# REV2.net
KiCad netlist of a schematic drawn in EAGLE
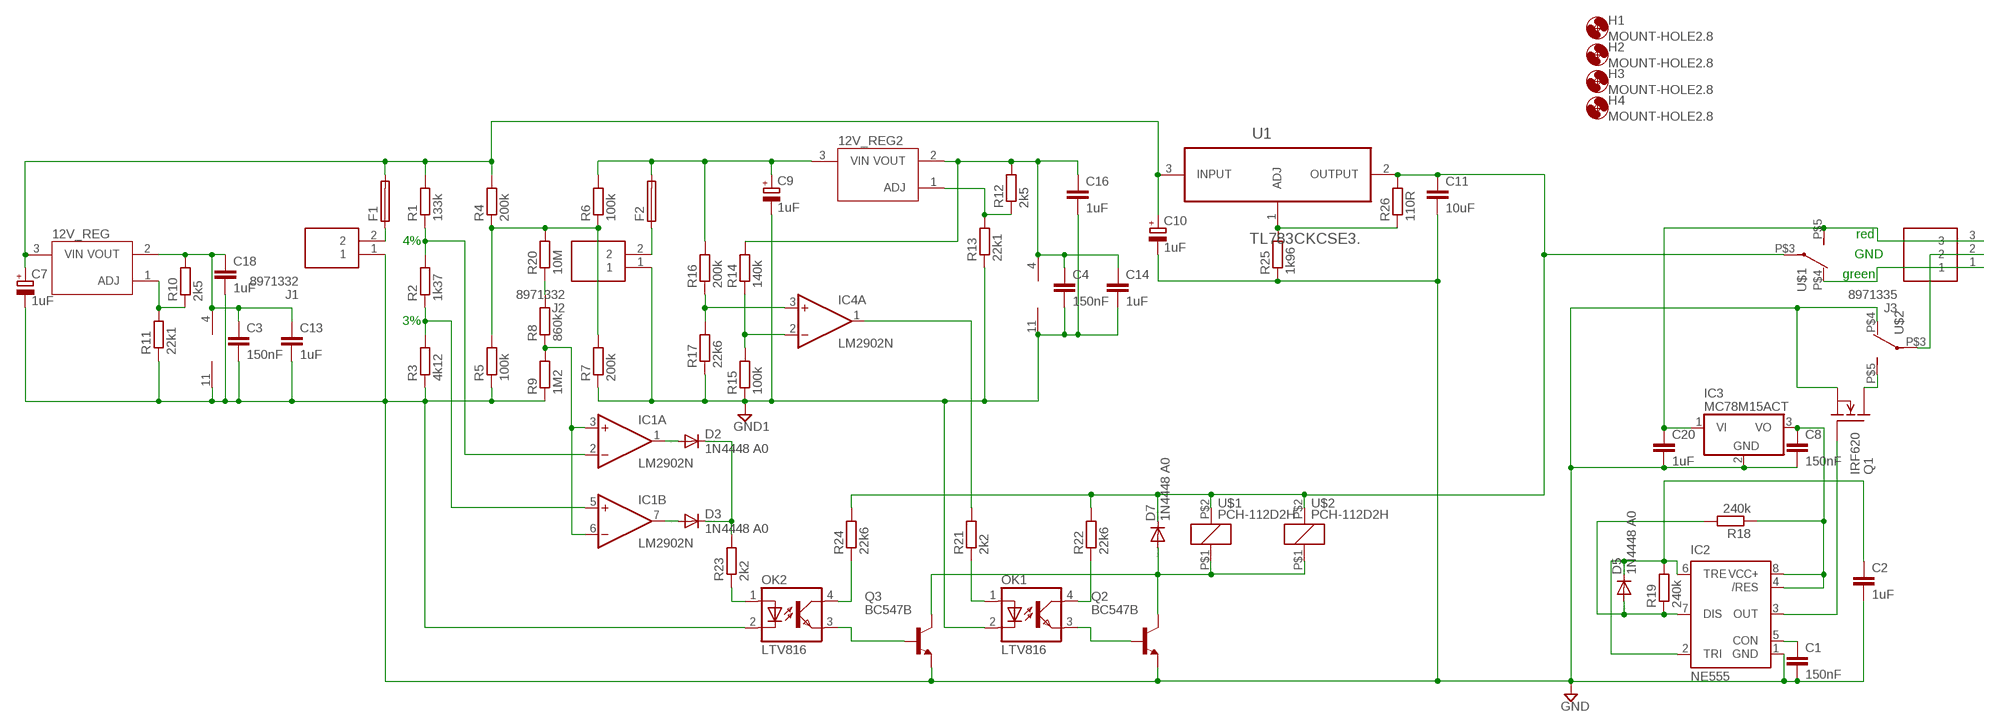
[diagram p0: schematic, sheet 1]

(export (version "E")
  (design (tool "Eeschema 10.0.6"))
  (components
    (comp (ref "12V_REG")
      (value "LR8LR8")
      (footprint "eagle-import:TO92-LINE")
      (libsource (lib "eagle-import") (part "LR8LR8"))
    )
    (comp (ref "12V_REG2")
      (value "LR8LR8")
      (footprint "eagle-import:TO92-LINE")
      (libsource (lib "eagle-import") (part "LR8LR8"))
    )
    (comp (ref "C1")
      (value "150nF")
      (footprint "eagle-import:C050-024X044")
      (libsource (lib "eagle-import") (part "C-EU050-024X044"))
    )
    (comp (ref "C2")
      (value "1uF")
      (footprint "eagle-import:C025-030X050")
      (libsource (lib "eagle-import") (part "C-EU025-030X050"))
    )
    (comp (ref "C3")
      (value "150nF")
      (footprint "eagle-import:C050-024X044")
      (libsource (lib "eagle-import") (part "C-EU050-024X044"))
    )
    (comp (ref "C4")
      (value "150nF")
      (footprint "eagle-import:C050-024X044")
      (libsource (lib "eagle-import") (part "C-EU050-024X044"))
    )
    (comp (ref "C7")
      (value "1uF")
      (footprint "eagle-import:E3,5-8")
      (libsource (lib "eagle-import") (part "CPOL-EUE3.5-8"))
    )
    (comp (ref "C8")
      (value "150nF")
      (footprint "eagle-import:C050-024X044")
      (libsource (lib "eagle-import") (part "C-EU050-024X044"))
    )
    (comp (ref "C9")
      (value "1uF")
      (footprint "eagle-import:E3,5-8")
      (libsource (lib "eagle-import") (part "CPOL-EUE3.5-8"))
    )
    (comp (ref "C10")
      (value "1uF")
      (footprint "eagle-import:E3,5-8")
      (libsource (lib "eagle-import") (part "CPOL-EUE3.5-8"))
    )
    (comp (ref "C11")
      (value "10uF")
      (footprint "eagle-import:C050-075X075")
      (libsource (lib "eagle-import") (part "C-EU050-075X075"))
    )
    (comp (ref "C13")
      (value "1uF")
      (footprint "eagle-import:C025-030X050")
      (libsource (lib "eagle-import") (part "C-EU025-030X050"))
    )
    (comp (ref "C14")
      (value "1uF")
      (footprint "eagle-import:C025-030X050")
      (libsource (lib "eagle-import") (part "C-EU025-030X050"))
    )
    (comp (ref "C16")
      (value "1uF")
      (footprint "eagle-import:C025-030X050")
      (libsource (lib "eagle-import") (part "C-EU025-030X050"))
    )
    (comp (ref "C18")
      (value "1uF")
      (footprint "eagle-import:C025-030X050")
      (libsource (lib "eagle-import") (part "C-EU025-030X050"))
    )
    (comp (ref "C20")
      (value "1uF")
      (footprint "eagle-import:C025-030X050")
      (libsource (lib "eagle-import") (part "C-EU025-030X050"))
    )
    (comp (ref "D2")
      (value "1N4448 A0")
      (footprint "eagle-import:DO35-10")
      (libsource (lib "eagle-import") (part "1N4446"))
    )
    (comp (ref "D3")
      (value "1N4448 A0")
      (footprint "eagle-import:DO35-10")
      (libsource (lib "eagle-import") (part "1N4446"))
    )
    (comp (ref "D5")
      (value "1N4448 A0")
      (footprint "eagle-import:DO35-10")
      (libsource (lib "eagle-import") (part "1N4446"))
    )
    (comp (ref "D7")
      (value "1N4448 A0")
      (footprint "eagle-import:DO35-10")
      (libsource (lib "eagle-import") (part "1N4446"))
    )
    (comp (ref "F1")
      (value "GSH15")
      (footprint "eagle-import:GSH15")
      (fields (field (name "MPN") "64900001039"))
      (libsource (lib "eagle-import") (part "GSH15"))
    )
    (comp (ref "F2")
      (value "GSH15")
      (footprint "eagle-import:GSH15")
      (fields (field (name "MPN") "64900001039"))
      (libsource (lib "eagle-import") (part "GSH15"))
    )
    (comp (ref "H1")
      (value "MOUNT-HOLE2.8")
      (footprint "eagle-import:2,8")
      (libsource (lib "eagle-import") (part "MOUNT-HOLE2.8"))
    )
    (comp (ref "H2")
      (value "MOUNT-HOLE2.8")
      (footprint "eagle-import:2,8")
      (libsource (lib "eagle-import") (part "MOUNT-HOLE2.8"))
    )
    (comp (ref "H3")
      (value "MOUNT-HOLE2.8")
      (footprint "eagle-import:2,8")
      (libsource (lib "eagle-import") (part "MOUNT-HOLE2.8"))
    )
    (comp (ref "H4")
      (value "MOUNT-HOLE2.8")
      (footprint "eagle-import:2,8")
      (libsource (lib "eagle-import") (part "MOUNT-HOLE2.8"))
    )
    (comp (ref "IC1")
      (value "LM2902N")
      (footprint "eagle-import:DIL14")
      (libsource (lib "eagle-import") (part "LM2902N"))
    )
    (comp (ref "IC2")
      (value "NE555")
      (footprint "eagle-import:DIL-08")
      (fields (field (name "MF") "Arrow Electronics") (field (name "MPN") "NE555N"))
      (libsource (lib "eagle-import") (part "NE555"))
    )
    (comp (ref "IC3")
      (value "MC78M15ACT")
      (footprint "eagle-import:TO220V")
      (libsource (lib "eagle-import") (part "MC78MT15AC"))
    )
    (comp (ref "IC4")
      (value "LM2902N")
      (footprint "eagle-import:DIL14")
      (libsource (lib "eagle-import") (part "LM2902N"))
    )
    (comp (ref "J1")
      (value "8971332")
      (footprint "eagle-import:SHDR2W90P0X350_1X2_700X700X850")
      (libsource (lib "eagle-import") (part "8971332"))
    )
    (comp (ref "J2")
      (value "8971332")
      (footprint "eagle-import:SHDR2W90P0X350_1X2_700X700X850")
      (libsource (lib "eagle-import") (part "8971332"))
    )
    (comp (ref "J3")
      (value "8971335")
      (footprint "eagle-import:SHDR3W90P0X350_1X3_1050X700X85")
      (libsource (lib "eagle-import") (part "8971335"))
    )
    (comp (ref "OK1")
      (value "LTV816")
      (footprint "eagle-import:DIL04")
      (libsource (lib "eagle-import") (part "LTV816"))
    )
    (comp (ref "OK2")
      (value "LTV816")
      (footprint "eagle-import:DIL04")
      (libsource (lib "eagle-import") (part "LTV816"))
    )
    (comp (ref "Q1")
      (value "IRF620")
      (footprint "eagle-import:TO220")
      (libsource (lib "eagle-import") (part "IRF620"))
    )
    (comp (ref "Q2")
      (value "BC547B")
      (footprint "eagle-import:TO92")
      (libsource (lib "eagle-import") (part "BC547B"))
    )
    (comp (ref "Q3")
      (value "BC547B")
      (footprint "eagle-import:TO92")
      (libsource (lib "eagle-import") (part "BC547B"))
    )
    (comp (ref "R1")
      (value "133k")
      (footprint "eagle-import:0207_10")
      (libsource (lib "eagle-import") (part "R-EU_0207/10"))
    )
    (comp (ref "R2")
      (value "1k37")
      (footprint "eagle-import:0207_10")
      (libsource (lib "eagle-import") (part "R-EU_0207/10"))
    )
    (comp (ref "R3")
      (value "4k12")
      (footprint "eagle-import:0207_10")
      (libsource (lib "eagle-import") (part "R-EU_0207/10"))
    )
    (comp (ref "R4")
      (value "200k")
      (footprint "eagle-import:0207_10")
      (libsource (lib "eagle-import") (part "R-EU_0207/10"))
    )
    (comp (ref "R5")
      (value "100k")
      (footprint "eagle-import:0207_10")
      (libsource (lib "eagle-import") (part "R-EU_0207/10"))
    )
    (comp (ref "R6")
      (value "100k")
      (footprint "eagle-import:0207_10")
      (libsource (lib "eagle-import") (part "R-EU_0207/10"))
    )
    (comp (ref "R7")
      (value "200k")
      (footprint "eagle-import:0207_10")
      (libsource (lib "eagle-import") (part "R-EU_0207/10"))
    )
    (comp (ref "R8")
      (value "860k")
      (footprint "eagle-import:0207_10")
      (libsource (lib "eagle-import") (part "R-EU_0207/10"))
    )
    (comp (ref "R9")
      (value "1M2")
      (footprint "eagle-import:0207_10")
      (libsource (lib "eagle-import") (part "R-EU_0207/10"))
    )
    (comp (ref "R10")
      (value "2k5")
      (footprint "eagle-import:0207_10")
      (libsource (lib "eagle-import") (part "R-EU_0207/10"))
    )
    (comp (ref "R11")
      (value "22k1")
      (footprint "eagle-import:0207_10")
      (libsource (lib "eagle-import") (part "R-EU_0207/10"))
    )
    (comp (ref "R12")
      (value "2k5")
      (footprint "eagle-import:0207_10")
      (libsource (lib "eagle-import") (part "R-EU_0207/10"))
    )
    (comp (ref "R13")
      (value "22k1")
      (footprint "eagle-import:0207_10")
      (libsource (lib "eagle-import") (part "R-EU_0207/10"))
    )
    (comp (ref "R14")
      (value "140k")
      (footprint "eagle-import:0207_10")
      (libsource (lib "eagle-import") (part "R-EU_0207/10"))
    )
    (comp (ref "R15")
      (value "100k")
      (footprint "eagle-import:0207_10")
      (libsource (lib "eagle-import") (part "R-EU_0207/10"))
    )
    (comp (ref "R16")
      (value "200k")
      (footprint "eagle-import:0207_10")
      (libsource (lib "eagle-import") (part "R-EU_0207/10"))
    )
    (comp (ref "R17")
      (value "22k6")
      (footprint "eagle-import:0207_10")
      (libsource (lib "eagle-import") (part "R-EU_0207/10"))
    )
    (comp (ref "R18")
      (value "240k")
      (footprint "eagle-import:0207_10")
      (libsource (lib "eagle-import") (part "R-EU_0207/10"))
    )
    (comp (ref "R19")
      (value "240k")
      (footprint "eagle-import:0207_10")
      (libsource (lib "eagle-import") (part "R-EU_0207/10"))
    )
    (comp (ref "R20")
      (value "10M")
      (footprint "eagle-import:0207_10")
      (libsource (lib "eagle-import") (part "R-EU_0207/10"))
    )
    (comp (ref "R21")
      (value "2k2")
      (footprint "eagle-import:0207_10")
      (libsource (lib "eagle-import") (part "R-EU_0207/10"))
    )
    (comp (ref "R22")
      (value "22k6")
      (footprint "eagle-import:0207_10")
      (libsource (lib "eagle-import") (part "R-EU_0207/10"))
    )
    (comp (ref "R23")
      (value "2k2")
      (footprint "eagle-import:0207_10")
      (libsource (lib "eagle-import") (part "R-EU_0207/10"))
    )
    (comp (ref "R24")
      (value "22k6")
      (footprint "eagle-import:0207_10")
      (libsource (lib "eagle-import") (part "R-EU_0207/10"))
    )
    (comp (ref "R25")
      (value "1k96")
      (footprint "eagle-import:0309_10")
      (libsource (lib "eagle-import") (part "R-EU_0309/10"))
    )
    (comp (ref "R26")
      (value "110R")
      (footprint "eagle-import:0309_10")
      (libsource (lib "eagle-import") (part "R-EU_0309/10"))
    )
    (comp (ref "U$1")
      (value "PCH-112D2H")
      (footprint "eagle-import:PCH-112D2H")
      (libsource (lib "eagle-import") (part "PCH-112D2H"))
    )
    (comp (ref "U$2")
      (value "PCH-112D2H")
      (footprint "eagle-import:PCH-112D2H")
      (libsource (lib "eagle-import") (part "PCH-112D2H"))
    )
    (comp (ref "U1")
      (value "TL783CKCSE3.")
      (footprint "eagle-import:TO254P457X1016X2222-3P")
      (libsource (lib "eagle-import") (part "TL783CKCSE3."))
    )
  )
  (nets
    (net (code "1") (name "GND") (class "Default")
      (node (ref "C1") (pin "2") (pinfunction "2_2") (pintype "passive"))
      (node (ref "C10") (pin "-") (pinfunction "-_-") (pintype "passive"))
      (node (ref "C11") (pin "2") (pinfunction "2_2") (pintype "passive"))
      (node (ref "C13") (pin "2") (pinfunction "2_2") (pintype "passive"))
      (node (ref "C18") (pin "2") (pinfunction "2_2") (pintype "passive"))
      (node (ref "C2") (pin "2") (pinfunction "2_2") (pintype "passive"))
      (node (ref "C20") (pin "2") (pinfunction "2_2") (pintype "passive"))
      (node (ref "C3") (pin "2") (pinfunction "2_2") (pintype "passive"))
      (node (ref "C7") (pin "-") (pinfunction "-_-") (pintype "passive"))
      (node (ref "C8") (pin "2") (pinfunction "2_2") (pintype "passive"))
      (node (ref "IC1") (pin "11") (pinfunction "V-_11") (pintype "power_in"))
      (node (ref "IC2") (pin "1") (pinfunction "GND_1") (pintype "power_in"))
      (node (ref "IC3") (pin "2") (pinfunction "GND_2") (pintype "passive"))
      (node (ref "J1") (pin "1") (pinfunction "1_1") (pintype "bidirectional"))
      (node (ref "OK2") (pin "2") (pinfunction "C_2") (pintype "passive"))
      (node (ref "Q1") (pin "3") (pinfunction "S_3") (pintype "passive"))
      (node (ref "Q2") (pin "1") (pinfunction "E_1") (pintype "passive"))
      (node (ref "Q3") (pin "1") (pinfunction "E_1") (pintype "passive"))
      (node (ref "R11") (pin "1") (pinfunction "1_1") (pintype "passive"))
      (node (ref "R25") (pin "1") (pinfunction "1_1") (pintype "passive"))
      (node (ref "R3") (pin "1") (pinfunction "1_1") (pintype "passive"))
      (node (ref "R5") (pin "1") (pinfunction "1_1") (pintype "passive"))
      (node (ref "R9") (pin "1") (pinfunction "1_1") (pintype "passive"))
      (node (ref "U$2") (pin "P$4") (pinfunction "O_P$4") (pintype "passive"))
    )
    (net (code "2") (name "GND1") (class "Default")
      (node (ref "C14") (pin "2") (pinfunction "2_2") (pintype "passive"))
      (node (ref "C16") (pin "2") (pinfunction "2_2") (pintype "passive"))
      (node (ref "C4") (pin "2") (pinfunction "2_2") (pintype "passive"))
      (node (ref "C9") (pin "-") (pinfunction "-_-") (pintype "passive"))
      (node (ref "IC4") (pin "11") (pinfunction "V-_11") (pintype "power_in"))
      (node (ref "J2") (pin "1") (pinfunction "1_1") (pintype "bidirectional"))
      (node (ref "OK1") (pin "2") (pinfunction "C_2") (pintype "passive"))
      (node (ref "R13") (pin "1") (pinfunction "1_1") (pintype "passive"))
      (node (ref "R15") (pin "1") (pinfunction "1_1") (pintype "passive"))
      (node (ref "R17") (pin "1") (pinfunction "1_1") (pintype "passive"))
      (node (ref "R7") (pin "1") (pinfunction "1_1") (pintype "passive"))
    )
    (net (code "3") (name "Net-(12V_REG-ADJ)") (class "Default")
      (node (ref "12V_REG") (pin "1") (pinfunction "ADJ_1") (pintype "bidirectional"))
      (node (ref "R10") (pin "1") (pinfunction "1_1") (pintype "passive"))
      (node (ref "R11") (pin "2") (pinfunction "2_2") (pintype "passive"))
    )
    (net (code "4") (name "Net-(12V_REG-VIN)") (class "Default")
      (node (ref "12V_REG") (pin "3") (pinfunction "VIN_3") (pintype "bidirectional"))
      (node (ref "C10") (pin "+") (pinfunction "+_+") (pintype "passive"))
      (node (ref "C7") (pin "+") (pinfunction "+_+") (pintype "passive"))
      (node (ref "F1") (pin "2") (pinfunction "2_2") (pintype "passive"))
      (node (ref "R1") (pin "2") (pinfunction "2_2") (pintype "passive"))
      (node (ref "R4") (pin "2") (pinfunction "2_2") (pintype "passive"))
      (node (ref "U1") (pin "3") (pinfunction "INPUT_3") (pintype "input"))
    )
    (net (code "5") (name "Net-(12V_REG-VOUT)") (class "Default")
      (node (ref "12V_REG") (pin "2") (pinfunction "VOUT_2") (pintype "bidirectional"))
      (node (ref "C13") (pin "1") (pinfunction "1_1") (pintype "passive"))
      (node (ref "C18") (pin "1") (pinfunction "1_1") (pintype "passive"))
      (node (ref "C3") (pin "1") (pinfunction "1_1") (pintype "passive"))
      (node (ref "IC1") (pin "4") (pinfunction "V+_4") (pintype "power_in"))
      (node (ref "R10") (pin "2") (pinfunction "2_2") (pintype "passive"))
    )
    (net (code "6") (name "Net-(12V_REG2-ADJ)") (class "Default")
      (node (ref "12V_REG2") (pin "1") (pinfunction "ADJ_1") (pintype "bidirectional"))
      (node (ref "R12") (pin "1") (pinfunction "1_1") (pintype "passive"))
      (node (ref "R13") (pin "2") (pinfunction "2_2") (pintype "passive"))
    )
    (net (code "7") (name "Net-(12V_REG2-VIN)") (class "Default")
      (node (ref "12V_REG2") (pin "3") (pinfunction "VIN_3") (pintype "bidirectional"))
      (node (ref "C9") (pin "+") (pinfunction "+_+") (pintype "passive"))
      (node (ref "F2") (pin "2") (pinfunction "2_2") (pintype "passive"))
      (node (ref "R16") (pin "2") (pinfunction "2_2") (pintype "passive"))
      (node (ref "R6") (pin "2") (pinfunction "2_2") (pintype "passive"))
    )
    (net (code "8") (name "Net-(12V_REG2-VOUT)") (class "Default")
      (node (ref "12V_REG2") (pin "2") (pinfunction "VOUT_2") (pintype "bidirectional"))
      (node (ref "C14") (pin "1") (pinfunction "1_1") (pintype "passive"))
      (node (ref "C16") (pin "1") (pinfunction "1_1") (pintype "passive"))
      (node (ref "C4") (pin "1") (pinfunction "1_1") (pintype "passive"))
      (node (ref "IC4") (pin "4") (pinfunction "V+_4") (pintype "power_in"))
      (node (ref "R12") (pin "2") (pinfunction "2_2") (pintype "passive"))
      (node (ref "R14") (pin "2") (pinfunction "2_2") (pintype "passive"))
    )
    (net (code "9") (name "Net-(D2-PadC)") (class "Default")
      (node (ref "D2") (pin "C") (pinfunction "C_C") (pintype "passive"))
      (node (ref "D3") (pin "C") (pinfunction "C_C") (pintype "passive"))
      (node (ref "R23") (pin "2") (pinfunction "2_2") (pintype "passive"))
    )
    (net (code "10") (name "Net-(F1-Pad1)") (class "Default")
      (node (ref "F1") (pin "1") (pinfunction "1_1") (pintype "passive"))
      (node (ref "J1") (pin "2") (pinfunction "2_2") (pintype "bidirectional"))
    )
    (net (code "11") (name "Net-(F2-Pad1)") (class "Default")
      (node (ref "F2") (pin "1") (pinfunction "1_1") (pintype "passive"))
      (node (ref "J2") (pin "2") (pinfunction "2_2") (pintype "bidirectional"))
    )
    (net (code "12") (name "Net-(IC1A-+IN)") (class "Default")
      (node (ref "IC1") (pin "3") (pinfunction "+IN_3") (pintype "input"))
      (node (ref "IC1") (pin "6") (pinfunction "-IN_6") (pintype "input"))
      (node (ref "R8") (pin "1") (pinfunction "1_1") (pintype "passive"))
      (node (ref "R9") (pin "2") (pinfunction "2_2") (pintype "passive"))
    )
    (net (code "13") (name "Net-(IC1A--IN)") (class "Default")
      (node (ref "IC1") (pin "2") (pinfunction "-IN_2") (pintype "input"))
      (node (ref "R1") (pin "1") (pinfunction "1_1") (pintype "passive"))
      (node (ref "R2") (pin "2") (pinfunction "2_2") (pintype "passive"))
    )
    (net (code "14") (name "Net-(IC1A-OUT)") (class "Default")
      (node (ref "D2") (pin "A") (pinfunction "A_A") (pintype "passive"))
      (node (ref "IC1") (pin "1") (pinfunction "OUT_1") (pintype "output"))
    )
    (net (code "15") (name "Net-(IC1B-+IN)") (class "Default")
      (node (ref "IC1") (pin "5") (pinfunction "+IN_5") (pintype "input"))
      (node (ref "R2") (pin "1") (pinfunction "1_1") (pintype "passive"))
      (node (ref "R3") (pin "2") (pinfunction "2_2") (pintype "passive"))
    )
    (net (code "16") (name "Net-(IC1B-OUT)") (class "Default")
      (node (ref "D3") (pin "A") (pinfunction "A_A") (pintype "passive"))
      (node (ref "IC1") (pin "7") (pinfunction "OUT_7") (pintype "output"))
    )
    (net (code "17") (name "Net-(IC2-CON)") (class "Default")
      (node (ref "C1") (pin "1") (pinfunction "1_1") (pintype "passive"))
      (node (ref "IC2") (pin "5") (pinfunction "CON_5") (pintype "input"))
    )
    (net (code "18") (name "Net-(IC2-DIS)") (class "Default")
      (node (ref "D5") (pin "A") (pinfunction "A_A") (pintype "passive"))
      (node (ref "IC2") (pin "7") (pinfunction "DIS_7") (pintype "input"))
      (node (ref "R18") (pin "2") (pinfunction "2_2") (pintype "passive"))
      (node (ref "R19") (pin "1") (pinfunction "1_1") (pintype "passive"))
    )
    (net (code "19") (name "Net-(IC2-OUT)") (class "Default")
      (node (ref "IC2") (pin "3") (pinfunction "OUT_3") (pintype "output"))
      (node (ref "Q1") (pin "1") (pinfunction "G_1") (pintype "passive"))
    )
    (net (code "20") (name "Net-(IC2-TRE)") (class "Default")
      (node (ref "C2") (pin "1") (pinfunction "1_1") (pintype "passive"))
      (node (ref "D5") (pin "C") (pinfunction "C_C") (pintype "passive"))
      (node (ref "IC2") (pin "2") (pinfunction "TRI_2") (pintype "input"))
      (node (ref "IC2") (pin "6") (pinfunction "TRE_6") (pintype "input"))
      (node (ref "R19") (pin "2") (pinfunction "2_2") (pintype "passive"))
    )
    (net (code "21") (name "Net-(IC2-VCC+)") (class "Default")
      (node (ref "C8") (pin "1") (pinfunction "1_1") (pintype "passive"))
      (node (ref "IC2") (pin "4") (pinfunction "/RES_4") (pintype "input"))
      (node (ref "IC2") (pin "8") (pinfunction "VCC+_8") (pintype "power_in"))
      (node (ref "IC3") (pin "3") (pinfunction "VO_3") (pintype "passive"))
      (node (ref "R18") (pin "1") (pinfunction "1_1") (pintype "passive"))
    )
    (net (code "22") (name "Net-(IC3-VI)") (class "Default")
      (node (ref "C20") (pin "1") (pinfunction "1_1") (pintype "passive"))
      (node (ref "IC3") (pin "1") (pinfunction "VI_1") (pintype "input"))
      (node (ref "J3") (pin "3") (pinfunction "3_3") (pintype "bidirectional"))
      (node (ref "U$1") (pin "P$5") (pinfunction "S_P$5") (pintype "passive"))
    )
    (net (code "23") (name "Net-(IC4A-+IN)") (class "Default")
      (node (ref "IC4") (pin "3") (pinfunction "+IN_3") (pintype "input"))
      (node (ref "R16") (pin "1") (pinfunction "1_1") (pintype "passive"))
      (node (ref "R17") (pin "2") (pinfunction "2_2") (pintype "passive"))
    )
    (net (code "24") (name "Net-(IC4A--IN)") (class "Default")
      (node (ref "IC4") (pin "2") (pinfunction "-IN_2") (pintype "input"))
      (node (ref "R14") (pin "1") (pinfunction "1_1") (pintype "passive"))
      (node (ref "R15") (pin "2") (pinfunction "2_2") (pintype "passive"))
    )
    (net (code "25") (name "Net-(IC4A-OUT)") (class "Default")
      (node (ref "IC4") (pin "1") (pinfunction "OUT_1") (pintype "output"))
      (node (ref "R21") (pin "2") (pinfunction "2_2") (pintype "passive"))
    )
    (net (code "26") (name "Net-(OK1-A)") (class "Default")
      (node (ref "OK1") (pin "1") (pinfunction "A_1") (pintype "passive"))
      (node (ref "R21") (pin "1") (pinfunction "1_1") (pintype "passive"))
    )
    (net (code "27") (name "Net-(OK1-COL)") (class "Default")
      (node (ref "OK1") (pin "4") (pinfunction "COL_4") (pintype "passive"))
      (node (ref "R22") (pin "1") (pinfunction "1_1") (pintype "passive"))
    )
    (net (code "28") (name "Net-(OK1-EMIT)") (class "Default")
      (node (ref "OK1") (pin "3") (pinfunction "EMIT_3") (pintype "passive"))
      (node (ref "Q2") (pin "2") (pinfunction "B_2") (pintype "passive"))
    )
    (net (code "29") (name "Net-(OK2-A)") (class "Default")
      (node (ref "OK2") (pin "1") (pinfunction "A_1") (pintype "passive"))
      (node (ref "R23") (pin "1") (pinfunction "1_1") (pintype "passive"))
    )
    (net (code "30") (name "Net-(OK2-COL)") (class "Default")
      (node (ref "OK2") (pin "4") (pinfunction "COL_4") (pintype "passive"))
      (node (ref "R24") (pin "1") (pinfunction "1_1") (pintype "passive"))
    )
    (net (code "31") (name "Net-(OK2-EMIT)") (class "Default")
      (node (ref "OK2") (pin "3") (pinfunction "EMIT_3") (pintype "passive"))
      (node (ref "Q3") (pin "2") (pinfunction "B_2") (pintype "passive"))
    )
    (net (code "32") (name "Net-(Q1-D)") (class "Default")
      (node (ref "Q1") (pin "2") (pinfunction "D_2") (pintype "passive"))
      (node (ref "U$2") (pin "P$5") (pinfunction "S_P$5") (pintype "passive"))
    )
    (net (code "33") (name "Net-(Q2-C)") (class "Default")
      (node (ref "D7") (pin "A") (pinfunction "A_A") (pintype "passive"))
      (node (ref "Q2") (pin "3") (pinfunction "C_3") (pintype "passive"))
      (node (ref "Q3") (pin "3") (pinfunction "C_3") (pintype "passive"))
      (node (ref "U$1") (pin "P$1") (pinfunction "2_P$1") (pintype "passive"))
      (node (ref "U$2") (pin "P$1") (pinfunction "2_P$1") (pintype "passive"))
    )
    (net (code "34") (name "Net-(R20-Pad1)") (class "Default")
      (node (ref "R20") (pin "1") (pinfunction "1_1") (pintype "passive"))
      (node (ref "R8") (pin "2") (pinfunction "2_2") (pintype "passive"))
    )
    (net (code "35") (name "Net-(R20-Pad2)") (class "Default")
      (node (ref "R20") (pin "2") (pinfunction "2_2") (pintype "passive"))
      (node (ref "R4") (pin "1") (pinfunction "1_1") (pintype "passive"))
      (node (ref "R5") (pin "2") (pinfunction "2_2") (pintype "passive"))
      (node (ref "R6") (pin "1") (pinfunction "1_1") (pintype "passive"))
      (node (ref "R7") (pin "2") (pinfunction "2_2") (pintype "passive"))
    )
    (net (code "36") (name "Net-(U$1A-1)") (class "Default")
      (node (ref "C11") (pin "1") (pinfunction "1_1") (pintype "passive"))
      (node (ref "D7") (pin "C") (pinfunction "C_C") (pintype "passive"))
      (node (ref "R22") (pin "2") (pinfunction "2_2") (pintype "passive"))
      (node (ref "R24") (pin "2") (pinfunction "2_2") (pintype "passive"))
      (node (ref "R26") (pin "2") (pinfunction "2_2") (pintype "passive"))
      (node (ref "U$1") (pin "P$2") (pinfunction "1_P$2") (pintype "passive"))
      (node (ref "U$1") (pin "P$3") (pinfunction "P_P$3") (pintype "passive"))
      (node (ref "U$2") (pin "P$2") (pinfunction "1_P$2") (pintype "passive"))
      (node (ref "U1") (pin "2") (pinfunction "OUTPUT_2") (pintype "output"))
    )
    (net (code "37") (name "Net-(U$1B-O)") (class "Default")
      (node (ref "J3") (pin "1") (pinfunction "1_1") (pintype "bidirectional"))
      (node (ref "U$1") (pin "P$4") (pinfunction "O_P$4") (pintype "passive"))
    )
    (net (code "38") (name "Net-(U$2B-P)") (class "Default")
      (node (ref "J3") (pin "2") (pinfunction "2_2") (pintype "bidirectional"))
      (node (ref "U$2") (pin "P$3") (pinfunction "P_P$3") (pintype "passive"))
    )
    (net (code "39") (name "Net-(U1-ADJ)") (class "Default")
      (node (ref "R25") (pin "2") (pinfunction "2_2") (pintype "passive"))
      (node (ref "R26") (pin "1") (pinfunction "1_1") (pintype "passive"))
      (node (ref "U1") (pin "1") (pinfunction "ADJ_1") (pintype "passive"))
    )
  )
)
